# v1.net
KiCad netlist of a schematic drawn in EAGLE
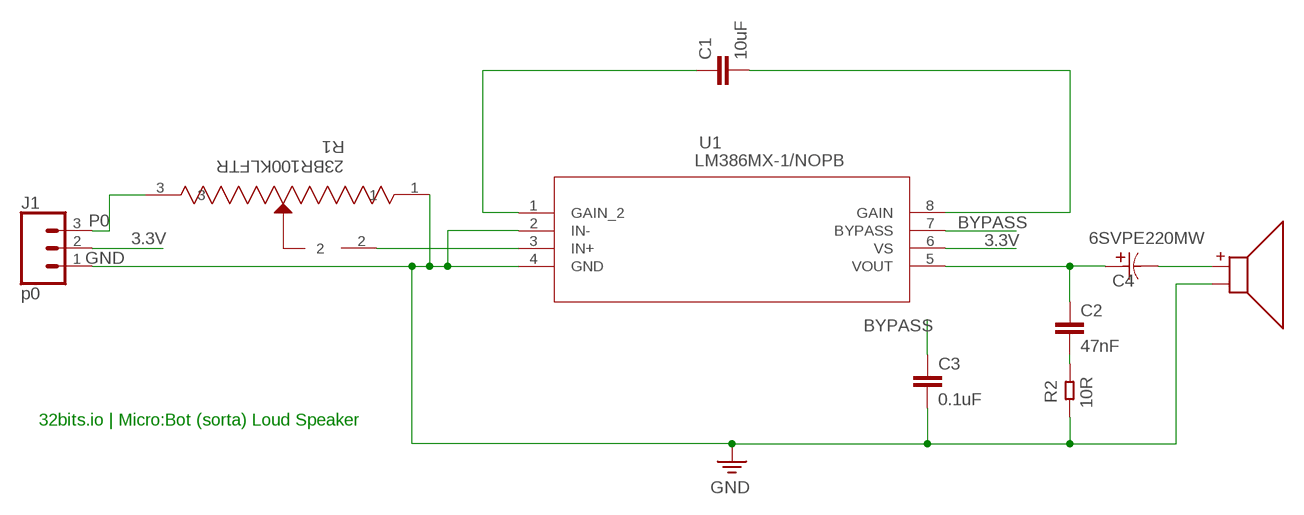
[diagram p0: schematic, sheet 1]

(export (version "E")
  (design (tool "Eeschema 10.0.6"))
  (components
    (comp (ref "C1")
      (value "10uF")
      (footprint "eagle-import:0603")
      (libsource (lib "eagle-import") (part "10UF-0603-6.3V-20%"))
    )
    (comp (ref "C2")
      (value "47nF")
      (footprint "eagle-import:0603")
      (libsource (lib "eagle-import") (part "47NF-0603-25V-5%"))
    )
    (comp (ref "C3")
      (value "0.1uF")
      (footprint "eagle-import:0603")
      (libsource (lib "eagle-import") (part "0.1UF-0603-25V-(+80/-20%)"))
    )
    (comp (ref "C4")
      (value "6SVPE220MW")
      (footprint "eagle-import:PCAP_SVP_B6")
      (libsource (lib "eagle-import") (part "6SVPE220MW"))
    )
    (comp (ref "J1")
      (value "p0")
      (footprint "eagle-import:1X03_SMD_RA_MALE")
      (libsource (lib "eagle-import") (part "CONN_03SMD_RA_MALE"))
    )
    (comp (ref "R1")
      (value "23BR100KLFTR")
      (footprint "eagle-import:SOT_23BR100KLFTR")
      (libsource (lib "eagle-import") (part "23BR100KLFTR"))
    )
    (comp (ref "R2")
      (value "10R")
      (footprint "eagle-import:R0603")
      (fields (field (name "MPN") "RC0603JR-070RL"))
      (libsource (lib "eagle-import") (part "SMD-RES-0R-5%-1/10W(0603)"))
    )
    (comp (ref "U$1")
      (value "SMS-1308MS-2-R")
      (footprint "eagle-import:SMS-1308MS-2-R")
      (libsource (lib "eagle-import") (part "SMS-1308MS-2-R"))
    )
    (comp (ref "U1")
      (value "LM386MX-1/NOPB")
      (footprint "eagle-import:M08A")
      (fields (field (name "MANUFACTURER_PART_NUMBER") "LM386MX1NOPB"))
      (libsource (lib "eagle-import") (part "LM386MX-1/NOPB"))
    )
  )
  (nets
    (net (code "1") (name "/3.3V") (class "Default")
      (node (ref "J1") (pin "2") (pinfunction "2_2") (pintype "passive"))
      (node (ref "U1") (pin "6") (pinfunction "VS_6") (pintype "power_in"))
    )
    (net (code "2") (name "/BYPASS") (class "Default")
      (node (ref "C3") (pin "1") (pinfunction "1_1") (pintype "passive"))
      (node (ref "U1") (pin "7") (pinfunction "BYPASS_7") (pintype "passive"))
    )
    (net (code "3") (name "/P0") (class "Default")
      (node (ref "J1") (pin "3") (pinfunction "3_3") (pintype "passive"))
      (node (ref "R1") (pin "3") (pinfunction "3_3") (pintype "passive"))
    )
    (net (code "4") (name "GND") (class "Default")
      (node (ref "C3") (pin "2") (pinfunction "2_2") (pintype "passive"))
      (node (ref "J1") (pin "1") (pinfunction "1_1") (pintype "passive"))
      (node (ref "R1") (pin "1") (pinfunction "1_1") (pintype "passive"))
      (node (ref "R2") (pin "1") (pinfunction "1_1") (pintype "passive"))
      (node (ref "U$1") (pin "-") (pinfunction "-_-") (pintype "bidirectional"))
      (node (ref "U1") (pin "2") (pinfunction "IN-_2") (pintype "input"))
      (node (ref "U1") (pin "4") (pinfunction "GND_4") (pintype "power_in"))
    )
    (net (code "5") (name "Net-(C2-Pad2)") (class "Default")
      (node (ref "C2") (pin "2") (pinfunction "2_2") (pintype "passive"))
      (node (ref "R2") (pin "2") (pinfunction "2_2") (pintype "passive"))
    )
    (net (code "6") (name "Net-(C4-11)") (class "Default")
      (node (ref "C2") (pin "1") (pinfunction "1_1") (pintype "passive"))
      (node (ref "C4") (pin "1") (pinfunction "11_1") (pintype "passive"))
      (node (ref "U1") (pin "5") (pinfunction "VOUT_5") (pintype "output"))
    )
    (net (code "7") (name "Net-(C4-22)") (class "Default")
      (node (ref "C4") (pin "2") (pinfunction "22_2") (pintype "passive"))
      (node (ref "U$1") (pin "+") (pinfunction "+_+") (pintype "bidirectional"))
    )
    (net (code "8") (name "Net-(U1-GAIN)") (class "Default")
      (node (ref "C1") (pin "2") (pinfunction "2_2") (pintype "passive"))
      (node (ref "U1") (pin "8") (pinfunction "GAIN_8") (pintype "passive"))
    )
    (net (code "9") (name "Net-(U1-GAIN_2)") (class "Default")
      (node (ref "C1") (pin "1") (pinfunction "1_1") (pintype "passive"))
      (node (ref "U1") (pin "1") (pinfunction "GAIN_2_1") (pintype "passive"))
    )
    (net (code "10") (name "Net-(U1-IN+)") (class "Default")
      (node (ref "R1") (pin "2") (pinfunction "2_2") (pintype "passive"))
      (node (ref "U1") (pin "3") (pinfunction "IN+_3") (pintype "input"))
    )
  )
)
